# SinclairScientificDisplay.net
KiCad netlist of a schematic drawn in EAGLE
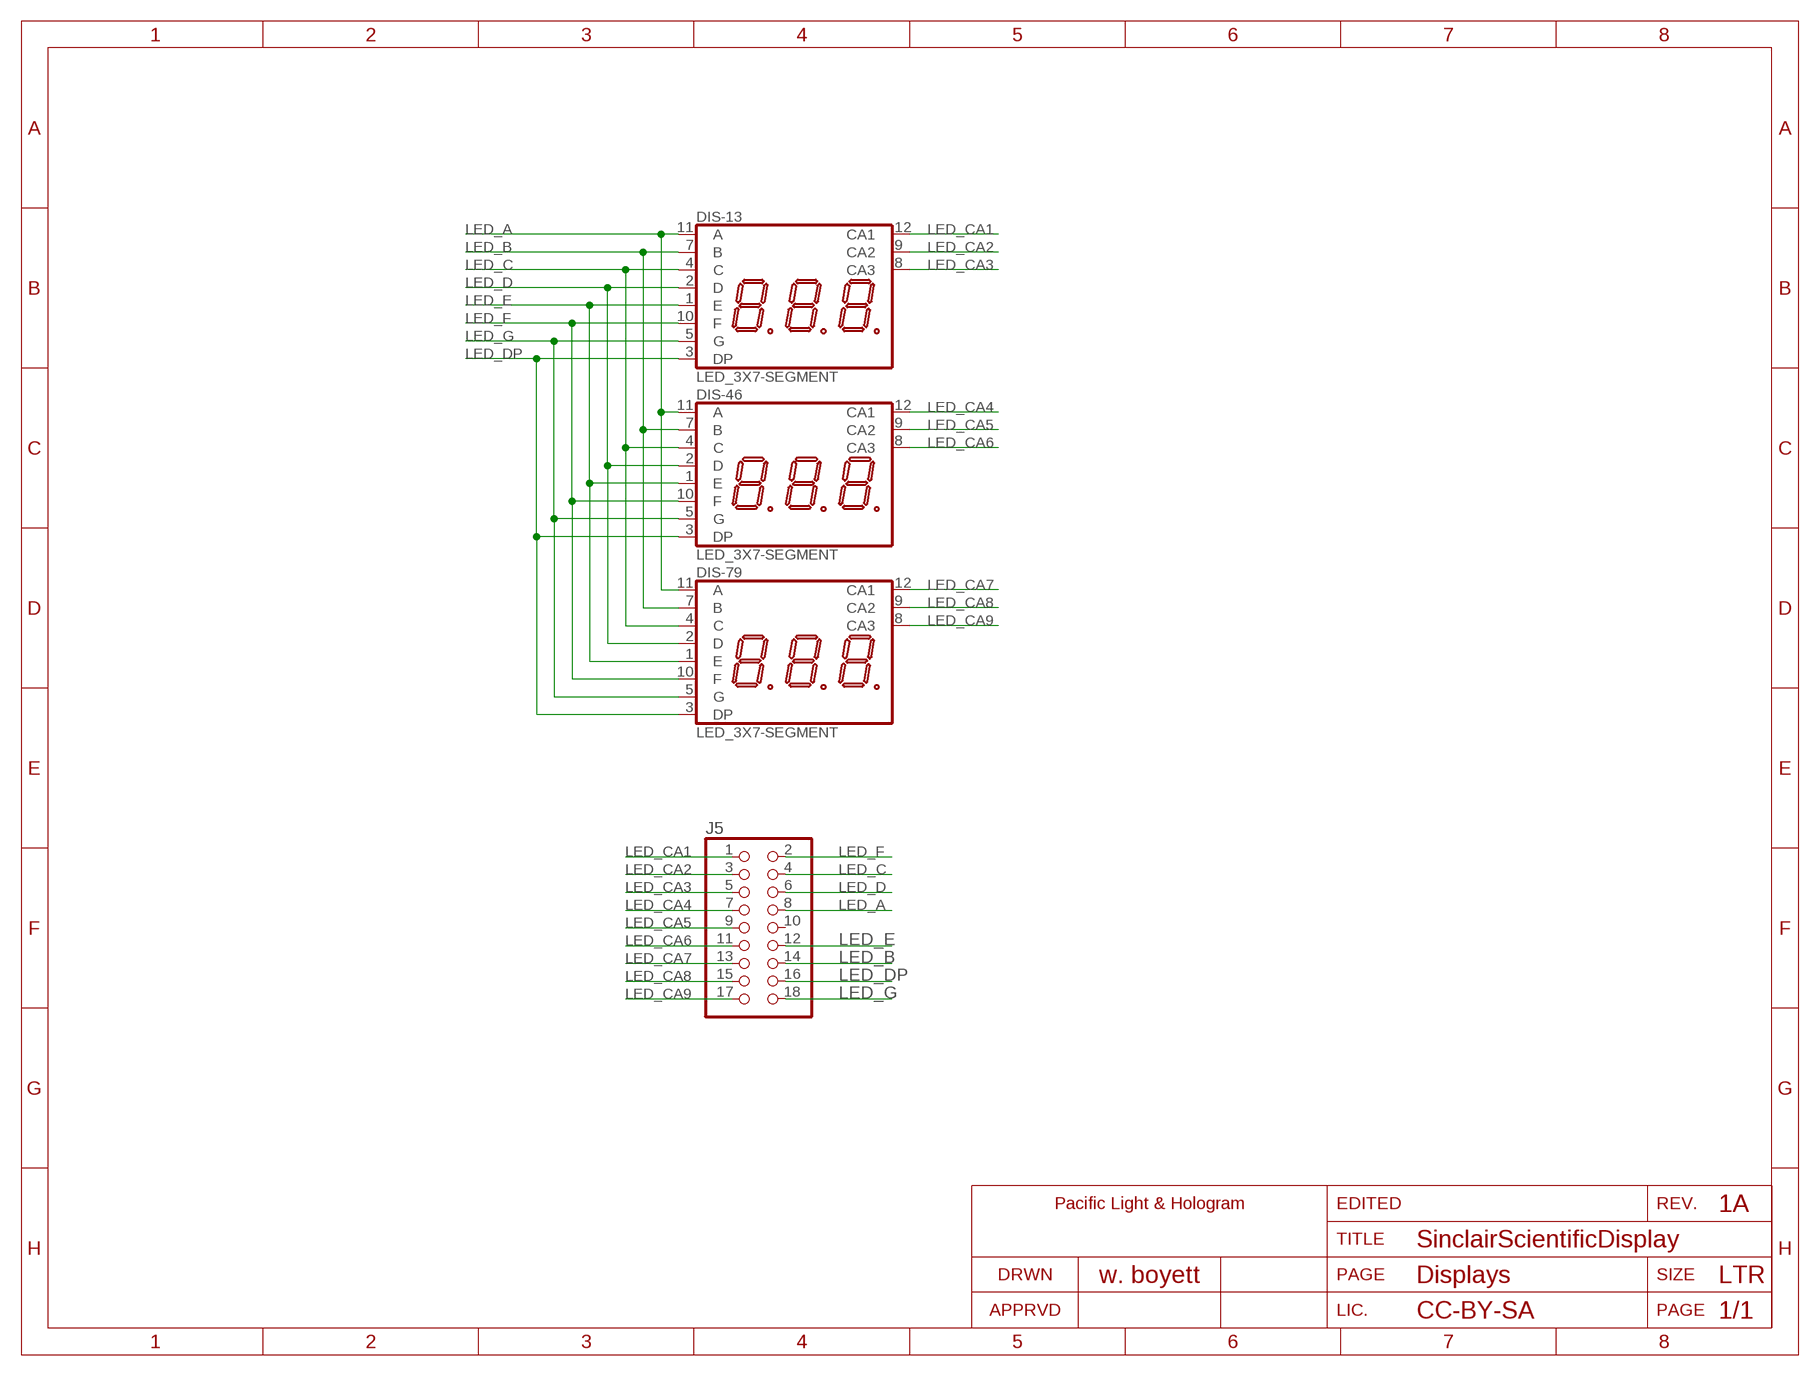
[diagram p0: schematic, sheet 1]

(export (version "E")
  (design (tool "Eeschema 10.0.6"))
  (components
    (comp (ref "DIS-13")
      (value "LED_3X7-SEGMENT")
      (footprint "eagle-import:2352B")
      (fields (field (name "SPICEPREFIX") "X"))
      (libsource (lib "eagle-import") (part "LED_3X7-SEGMENT"))
    )
    (comp (ref "DIS-46")
      (value "LED_3X7-SEGMENT")
      (footprint "eagle-import:2352B")
      (libsource (lib "eagle-import") (part "LED_3X7-SEGMENT"))
    )
    (comp (ref "DIS-79")
      (value "LED_3X7-SEGMENT")
      (footprint "eagle-import:2352B")
      (libsource (lib "eagle-import") (part "LED_3X7-SEGMENT"))
    )
    (comp (ref "J5")
      (value "PINHD-2X9-2MM")
      (footprint "eagle-import:2X09-2MM")
      (fields (field (name "MFG") "Molex"))
      (libsource (lib "eagle-import") (part "PINHD-2X9-2MM"))
    )
  )
  (nets
    (net (code "1") (name "/LED_A") (class "Default")
      (node (ref "DIS-13") (pin "11") (pinfunction "A_11") (pintype "passive"))
      (node (ref "DIS-46") (pin "11") (pinfunction "A_11") (pintype "passive"))
      (node (ref "DIS-79") (pin "11") (pinfunction "A_11") (pintype "passive"))
      (node (ref "J5") (pin "8") (pinfunction "8_8") (pintype "passive"))
    )
    (net (code "2") (name "/LED_B") (class "Default")
      (node (ref "DIS-13") (pin "7") (pinfunction "B_7") (pintype "passive"))
      (node (ref "DIS-46") (pin "7") (pinfunction "B_7") (pintype "passive"))
      (node (ref "DIS-79") (pin "7") (pinfunction "B_7") (pintype "passive"))
      (node (ref "J5") (pin "14") (pinfunction "14_14") (pintype "passive"))
    )
    (net (code "3") (name "/LED_C") (class "Default")
      (node (ref "DIS-13") (pin "4") (pinfunction "C_4") (pintype "passive"))
      (node (ref "DIS-46") (pin "4") (pinfunction "C_4") (pintype "passive"))
      (node (ref "DIS-79") (pin "4") (pinfunction "C_4") (pintype "passive"))
      (node (ref "J5") (pin "4") (pinfunction "4_4") (pintype "passive"))
    )
    (net (code "4") (name "/LED_CA1") (class "Default")
      (node (ref "DIS-13") (pin "12") (pinfunction "CA1_12") (pintype "passive"))
      (node (ref "J5") (pin "1") (pinfunction "1_1") (pintype "passive"))
    )
    (net (code "5") (name "/LED_CA2") (class "Default")
      (node (ref "DIS-13") (pin "9") (pinfunction "CA2_9") (pintype "passive"))
      (node (ref "J5") (pin "3") (pinfunction "3_3") (pintype "passive"))
    )
    (net (code "6") (name "/LED_CA3") (class "Default")
      (node (ref "DIS-13") (pin "8") (pinfunction "CA3_8") (pintype "passive"))
      (node (ref "J5") (pin "5") (pinfunction "5_5") (pintype "passive"))
    )
    (net (code "7") (name "/LED_CA4") (class "Default")
      (node (ref "DIS-46") (pin "12") (pinfunction "CA1_12") (pintype "passive"))
      (node (ref "J5") (pin "7") (pinfunction "7_7") (pintype "passive"))
    )
    (net (code "8") (name "/LED_CA5") (class "Default")
      (node (ref "DIS-46") (pin "9") (pinfunction "CA2_9") (pintype "passive"))
      (node (ref "J5") (pin "9") (pinfunction "9_9") (pintype "passive"))
    )
    (net (code "9") (name "/LED_CA6") (class "Default")
      (node (ref "DIS-46") (pin "8") (pinfunction "CA3_8") (pintype "passive"))
      (node (ref "J5") (pin "11") (pinfunction "11_11") (pintype "passive"))
    )
    (net (code "10") (name "/LED_CA7") (class "Default")
      (node (ref "DIS-79") (pin "12") (pinfunction "CA1_12") (pintype "passive"))
      (node (ref "J5") (pin "13") (pinfunction "13_13") (pintype "passive"))
    )
    (net (code "11") (name "/LED_CA8") (class "Default")
      (node (ref "DIS-79") (pin "9") (pinfunction "CA2_9") (pintype "passive"))
      (node (ref "J5") (pin "15") (pinfunction "15_15") (pintype "passive"))
    )
    (net (code "12") (name "/LED_CA9") (class "Default")
      (node (ref "DIS-79") (pin "8") (pinfunction "CA3_8") (pintype "passive"))
      (node (ref "J5") (pin "17") (pinfunction "17_17") (pintype "passive"))
    )
    (net (code "13") (name "/LED_D") (class "Default")
      (node (ref "DIS-13") (pin "2") (pinfunction "D_2") (pintype "passive"))
      (node (ref "DIS-46") (pin "2") (pinfunction "D_2") (pintype "passive"))
      (node (ref "DIS-79") (pin "2") (pinfunction "D_2") (pintype "passive"))
      (node (ref "J5") (pin "6") (pinfunction "6_6") (pintype "passive"))
    )
    (net (code "14") (name "/LED_DP") (class "Default")
      (node (ref "DIS-13") (pin "3") (pinfunction "DP_3") (pintype "passive"))
      (node (ref "DIS-46") (pin "3") (pinfunction "DP_3") (pintype "passive"))
      (node (ref "DIS-79") (pin "3") (pinfunction "DP_3") (pintype "passive"))
      (node (ref "J5") (pin "16") (pinfunction "16_16") (pintype "passive"))
    )
    (net (code "15") (name "/LED_E") (class "Default")
      (node (ref "DIS-13") (pin "1") (pinfunction "E_1") (pintype "passive"))
      (node (ref "DIS-46") (pin "1") (pinfunction "E_1") (pintype "passive"))
      (node (ref "DIS-79") (pin "1") (pinfunction "E_1") (pintype "passive"))
      (node (ref "J5") (pin "12") (pinfunction "12_12") (pintype "passive"))
    )
    (net (code "16") (name "/LED_F") (class "Default")
      (node (ref "DIS-13") (pin "10") (pinfunction "F_10") (pintype "passive"))
      (node (ref "DIS-46") (pin "10") (pinfunction "F_10") (pintype "passive"))
      (node (ref "DIS-79") (pin "10") (pinfunction "F_10") (pintype "passive"))
      (node (ref "J5") (pin "2") (pinfunction "2_2") (pintype "passive"))
    )
    (net (code "17") (name "/LED_G") (class "Default")
      (node (ref "DIS-13") (pin "5") (pinfunction "G_5") (pintype "passive"))
      (node (ref "DIS-46") (pin "5") (pinfunction "G_5") (pintype "passive"))
      (node (ref "DIS-79") (pin "5") (pinfunction "G_5") (pintype "passive"))
      (node (ref "J5") (pin "18") (pinfunction "18_18") (pintype "passive"))
    )
    (net (code "18") (name "unconnected-(J5-Pad10)") (class "Default")
      (node (ref "J5") (pin "10") (pinfunction "10_10") (pintype "passive"))
    )
  )
)
